# Park-A.net
KiCad netlist of a schematic drawn in EAGLE
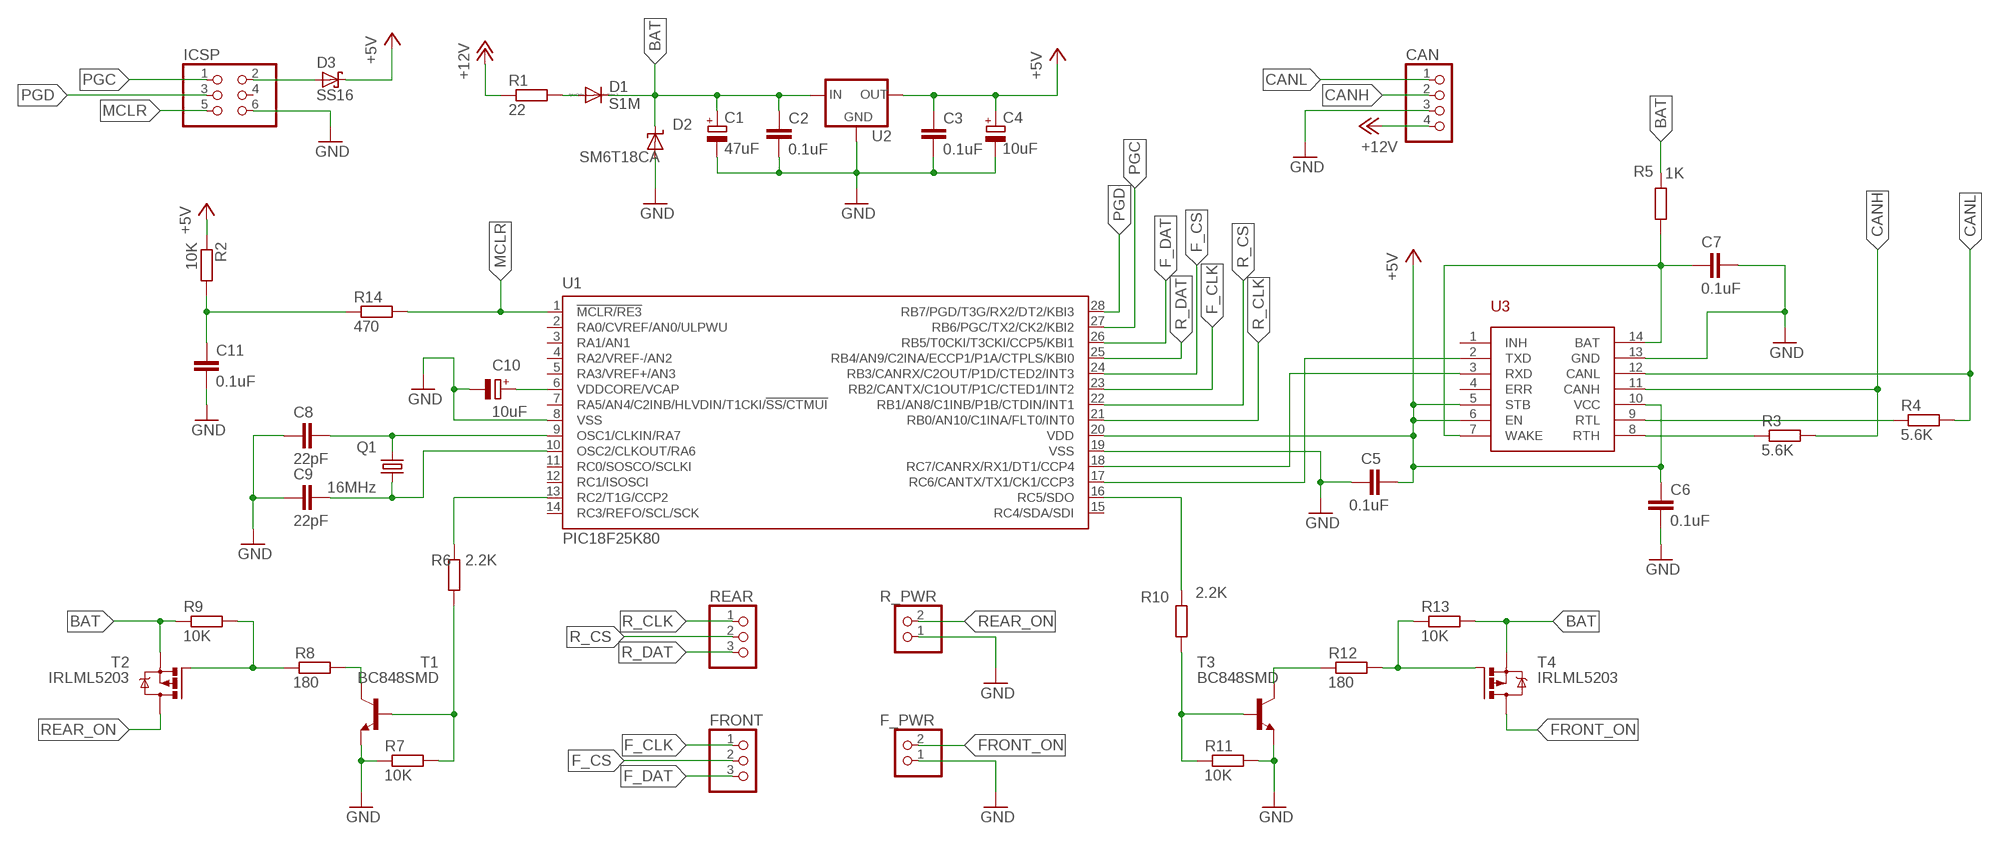
[diagram p0: schematic, sheet 1]

(export (version "E")
  (design (tool "Eeschema 10.0.6"))
  (components
    (comp (ref "C1")
      (value "47uF")
      (footprint "eagle-import:140CLH-0810")
      (libsource (lib "eagle-import") (part "CPOL-EU140CLH-0810"))
    )
    (comp (ref "C2")
      (value "0.1uF")
      (footprint "eagle-import:C0805")
      (libsource (lib "eagle-import") (part "C-EUC0805"))
    )
    (comp (ref "C3")
      (value "0.1uF")
      (footprint "eagle-import:C0805")
      (libsource (lib "eagle-import") (part "C-EUC0805"))
    )
    (comp (ref "C4")
      (value "10uF")
      (footprint "eagle-import:153CLV-0605")
      (libsource (lib "eagle-import") (part "CPOL-EU153CLV-0605"))
    )
    (comp (ref "C5")
      (value "0.1uF")
      (footprint "eagle-import:C0805")
      (libsource (lib "eagle-import") (part "C-EUC0805"))
    )
    (comp (ref "C6")
      (value "0.1uF")
      (footprint "eagle-import:C0805")
      (libsource (lib "eagle-import") (part "C-EUC0805"))
    )
    (comp (ref "C7")
      (value "0.1uF")
      (footprint "eagle-import:C0805")
      (libsource (lib "eagle-import") (part "C-EUC0805"))
    )
    (comp (ref "C8")
      (value "22pF")
      (footprint "eagle-import:C0805")
      (libsource (lib "eagle-import") (part "C-EUC0805"))
    )
    (comp (ref "C9")
      (value "22pF")
      (footprint "eagle-import:C0805")
      (libsource (lib "eagle-import") (part "C-EUC0805"))
    )
    (comp (ref "C10")
      (value "10uF")
      (footprint "eagle-import:SMC_A")
      (libsource (lib "eagle-import") (part "CPOL-EUSMCA"))
    )
    (comp (ref "C11")
      (value "0.1uF")
      (footprint "eagle-import:C0805")
      (libsource (lib "eagle-import") (part "C-EUC0805"))
    )
    (comp (ref "CAN")
      (value "PINHD-1X4")
      (footprint "eagle-import:1X04")
      (libsource (lib "eagle-import") (part "PINHD-1X4"))
    )
    (comp (ref "D1")
      (value "S1M")
      (footprint "eagle-import:SMA")
      (libsource (lib "eagle-import") (part "S1M"))
    )
    (comp (ref "D2")
      (value "SM6T18CA")
      (footprint "eagle-import:SMBJ")
      (libsource (lib "eagle-import") (part "SUPPRESSOR-SMBJ"))
    )
    (comp (ref "D3")
      (value "SS16")
      (footprint "eagle-import:DO214AC")
      (libsource (lib "eagle-import") (part "SS16"))
    )
    (comp (ref "FRONT")
      (value "PINHD-1X3")
      (footprint "eagle-import:1X03")
      (libsource (lib "eagle-import") (part "PINHD-1X3"))
    )
    (comp (ref "F_PWR")
      (value "PINHD-1X2")
      (footprint "eagle-import:1X02")
      (libsource (lib "eagle-import") (part "PINHD-1X2"))
    )
    (comp (ref "ICSP")
      (value "PINHD-2X3")
      (footprint "eagle-import:2X03")
      (libsource (lib "eagle-import") (part "PINHD-2X3"))
    )
    (comp (ref "Q1")
      (value "16MHz")
      (footprint "eagle-import:HC49_S")
      (libsource (lib "eagle-import") (part "CRYSTALHC49S"))
    )
    (comp (ref "R1")
      (value "22")
      (footprint "eagle-import:M1206")
      (libsource (lib "eagle-import") (part "R-EU_M1206"))
    )
    (comp (ref "R2")
      (value "10K")
      (footprint "eagle-import:R0805")
      (libsource (lib "eagle-import") (part "R-EU_R0805"))
    )
    (comp (ref "R3")
      (value "5.6K")
      (footprint "eagle-import:R0805")
      (libsource (lib "eagle-import") (part "R-EU_R0805"))
    )
    (comp (ref "R4")
      (value "5.6K")
      (footprint "eagle-import:R0805")
      (libsource (lib "eagle-import") (part "R-EU_R0805"))
    )
    (comp (ref "R5")
      (value "1K")
      (footprint "eagle-import:R0805")
      (libsource (lib "eagle-import") (part "R-EU_R0805"))
    )
    (comp (ref "R6")
      (value "2.2K")
      (footprint "eagle-import:R0805")
      (libsource (lib "eagle-import") (part "R-EU_R0805"))
    )
    (comp (ref "R7")
      (value "10K")
      (footprint "eagle-import:R0805")
      (libsource (lib "eagle-import") (part "R-EU_R0805"))
    )
    (comp (ref "R8")
      (value "180")
      (footprint "eagle-import:R0805")
      (libsource (lib "eagle-import") (part "R-EU_R0805"))
    )
    (comp (ref "R9")
      (value "10K")
      (footprint "eagle-import:R0805")
      (libsource (lib "eagle-import") (part "R-EU_R0805"))
    )
    (comp (ref "R10")
      (value "2.2K")
      (footprint "eagle-import:R0805")
      (libsource (lib "eagle-import") (part "R-EU_R0805"))
    )
    (comp (ref "R11")
      (value "10K")
      (footprint "eagle-import:R0805")
      (libsource (lib "eagle-import") (part "R-EU_R0805"))
    )
    (comp (ref "R12")
      (value "180")
      (footprint "eagle-import:R0805")
      (libsource (lib "eagle-import") (part "R-EU_R0805"))
    )
    (comp (ref "R13")
      (value "10K")
      (footprint "eagle-import:R0805")
      (libsource (lib "eagle-import") (part "R-EU_R0805"))
    )
    (comp (ref "R14")
      (value "470")
      (footprint "eagle-import:R0805")
      (libsource (lib "eagle-import") (part "R-EU_R0805"))
    )
    (comp (ref "REAR")
      (value "PINHD-1X3")
      (footprint "eagle-import:1X03")
      (libsource (lib "eagle-import") (part "PINHD-1X3"))
    )
    (comp (ref "R_PWR")
      (value "PINHD-1X2")
      (footprint "eagle-import:1X02")
      (libsource (lib "eagle-import") (part "PINHD-1X2"))
    )
    (comp (ref "T1")
      (value "BC848SMD")
      (footprint "eagle-import:SOT23")
      (libsource (lib "eagle-import") (part "BC848SMD"))
    )
    (comp (ref "T2")
      (value "IRLML5203")
      (footprint "eagle-import:SOT23")
      (libsource (lib "eagle-import") (part "IRLML5203"))
    )
    (comp (ref "T3")
      (value "BC848SMD")
      (footprint "eagle-import:SOT23")
      (libsource (lib "eagle-import") (part "BC848SMD"))
    )
    (comp (ref "T4")
      (value "IRLML5203")
      (footprint "eagle-import:SOT23")
      (libsource (lib "eagle-import") (part "IRLML5203"))
    )
    (comp (ref "U1")
      (value "PIC18F25K80")
      (footprint "eagle-import:SO28W")
      (libsource (lib "eagle-import") (part "PIC18F25K80"))
    )
    (comp (ref "U2")
      (value "78M05")
      (footprint "eagle-import:DPACK")
      (libsource (lib "eagle-import") (part "78M05"))
    )
    (comp (ref "U3")
      (value "TJA1055T")
      (footprint "eagle-import:SO-14W")
      (libsource (lib "eagle-import") (part "TJA1055T"))
    )
  )
  (nets
    (net (code "1") (name "+5V") (class "Default")
      (node (ref "C3") (pin "1") (pinfunction "1_1") (pintype "passive"))
      (node (ref "C4") (pin "+") (pinfunction "+_+") (pintype "passive"))
      (node (ref "C5") (pin "1") (pinfunction "1_1") (pintype "passive"))
      (node (ref "C6") (pin "1") (pinfunction "1_1") (pintype "passive"))
      (node (ref "D3") (pin "C") (pinfunction "C_C") (pintype "passive"))
      (node (ref "R2") (pin "1") (pinfunction "1_1") (pintype "passive"))
      (node (ref "U1") (pin "20") (pinfunction "VDD_20") (pintype "power_in"))
      (node (ref "U2") (pin "3") (pinfunction "OUT_3") (pintype "passive"))
      (node (ref "U3") (pin "10") (pinfunction "VCC_10") (pintype "power_in"))
      (node (ref "U3") (pin "5") (pinfunction "STB_5") (pintype "input"))
      (node (ref "U3") (pin "6") (pinfunction "EN_6") (pintype "input"))
    )
    (net (code "2") (name "+12V") (class "Default")
      (node (ref "CAN") (pin "4") (pinfunction "4_4") (pintype "passive"))
      (node (ref "R1") (pin "1") (pinfunction "1_1") (pintype "passive"))
    )
    (net (code "3") (name "BAT") (class "Default")
      (node (ref "C1") (pin "+") (pinfunction "+_+") (pintype "passive"))
      (node (ref "C2") (pin "1") (pinfunction "1_1") (pintype "passive"))
      (node (ref "D1") (pin "C") (pinfunction "C_C") (pintype "passive"))
      (node (ref "D2") (pin "C") (pinfunction "C_C") (pintype "passive"))
      (node (ref "R13") (pin "2") (pinfunction "2_2") (pintype "passive"))
      (node (ref "R5") (pin "2") (pinfunction "2_2") (pintype "passive"))
      (node (ref "R9") (pin "1") (pinfunction "1_1") (pintype "passive"))
      (node (ref "T2") (pin "2") (pinfunction "S_2") (pintype "passive"))
      (node (ref "T4") (pin "2") (pinfunction "S_2") (pintype "passive"))
      (node (ref "U2") (pin "1") (pinfunction "IN_1") (pintype "input"))
    )
    (net (code "4") (name "CANH") (class "Default")
      (node (ref "CAN") (pin "2") (pinfunction "2_2") (pintype "passive"))
      (node (ref "R3") (pin "2") (pinfunction "2_2") (pintype "passive"))
      (node (ref "U3") (pin "11") (pinfunction "CANH_11") (pintype "bidirectional"))
    )
    (net (code "5") (name "CANL") (class "Default")
      (node (ref "CAN") (pin "1") (pinfunction "1_1") (pintype "passive"))
      (node (ref "R4") (pin "2") (pinfunction "2_2") (pintype "passive"))
      (node (ref "U3") (pin "12") (pinfunction "CANL_12") (pintype "bidirectional"))
    )
    (net (code "6") (name "FRONT_ON") (class "Default")
      (node (ref "F_PWR") (pin "2") (pinfunction "2_2") (pintype "passive"))
      (node (ref "T4") (pin "3") (pinfunction "D_3") (pintype "passive"))
    )
    (net (code "7") (name "F_CLK") (class "Default")
      (node (ref "FRONT") (pin "1") (pinfunction "1_1") (pintype "passive"))
      (node (ref "U1") (pin "23") (pinfunction "RB2/CANTX/C1OUT/P1C/CTED1/INT2_23") (pintype "bidirectional"))
    )
    (net (code "8") (name "F_CS") (class "Default")
      (node (ref "FRONT") (pin "2") (pinfunction "2_2") (pintype "passive"))
      (node (ref "U1") (pin "24") (pinfunction "RB3/CANRX/C2OUT/P1D/CTED2/INT3_24") (pintype "bidirectional"))
    )
    (net (code "9") (name "F_DAT") (class "Default")
      (node (ref "FRONT") (pin "3") (pinfunction "3_3") (pintype "passive"))
      (node (ref "U1") (pin "26") (pinfunction "RB5/T0CKI/T3CKI/CCP5/KBI1_26") (pintype "bidirectional"))
    )
    (net (code "10") (name "GND") (class "Default")
      (node (ref "C1") (pin "-") (pinfunction "-_-") (pintype "passive"))
      (node (ref "C10") (pin "-") (pinfunction "-_-") (pintype "passive"))
      (node (ref "C11") (pin "2") (pinfunction "2_2") (pintype "passive"))
      (node (ref "C2") (pin "2") (pinfunction "2_2") (pintype "passive"))
      (node (ref "C3") (pin "2") (pinfunction "2_2") (pintype "passive"))
      (node (ref "C4") (pin "-") (pinfunction "-_-") (pintype "passive"))
      (node (ref "C5") (pin "2") (pinfunction "2_2") (pintype "passive"))
      (node (ref "C6") (pin "2") (pinfunction "2_2") (pintype "passive"))
      (node (ref "C7") (pin "2") (pinfunction "2_2") (pintype "passive"))
      (node (ref "C8") (pin "1") (pinfunction "1_1") (pintype "passive"))
      (node (ref "C9") (pin "1") (pinfunction "1_1") (pintype "passive"))
      (node (ref "CAN") (pin "3") (pinfunction "3_3") (pintype "passive"))
      (node (ref "D2") (pin "A") (pinfunction "A_A") (pintype "passive"))
      (node (ref "F_PWR") (pin "1") (pinfunction "1_1") (pintype "passive"))
      (node (ref "ICSP") (pin "6") (pinfunction "6_6") (pintype "passive"))
      (node (ref "R11") (pin "2") (pinfunction "2_2") (pintype "passive"))
      (node (ref "R7") (pin "1") (pinfunction "1_1") (pintype "passive"))
      (node (ref "R_PWR") (pin "1") (pinfunction "1_1") (pintype "passive"))
      (node (ref "T1") (pin "2") (pinfunction "E_2") (pintype "passive"))
      (node (ref "T3") (pin "2") (pinfunction "E_2") (pintype "passive"))
      (node (ref "U1") (pin "19") (pinfunction "VSS_19") (pintype "power_in"))
      (node (ref "U1") (pin "8") (pinfunction "VSS_8") (pintype "power_in"))
      (node (ref "U2") (pin "4") (pinfunction "GND_4") (pintype "input"))
      (node (ref "U3") (pin "13") (pinfunction "GND_13") (pintype "power_in"))
    )
    (net (code "11") (name "MCLR") (class "Default")
      (node (ref "ICSP") (pin "5") (pinfunction "5_5") (pintype "passive"))
      (node (ref "R14") (pin "2") (pinfunction "2_2") (pintype "passive"))
      (node (ref "U1") (pin "1") (pinfunction "~{MCLR/RE3}_1") (pintype "input"))
    )
    (net (code "12") (name "Net-(C11-Pad1)") (class "Default")
      (node (ref "C11") (pin "1") (pinfunction "1_1") (pintype "passive"))
      (node (ref "R14") (pin "1") (pinfunction "1_1") (pintype "passive"))
      (node (ref "R2") (pin "2") (pinfunction "2_2") (pintype "passive"))
    )
    (net (code "13") (name "Net-(D1-PadA)") (class "Default")
      (node (ref "D1") (pin "A") (pinfunction "A_A") (pintype "passive"))
      (node (ref "R1") (pin "2") (pinfunction "2_2") (pintype "passive"))
    )
    (net (code "14") (name "Net-(D3-PadA)") (class "Default")
      (node (ref "D3") (pin "A") (pinfunction "A_A") (pintype "passive"))
      (node (ref "ICSP") (pin "2") (pinfunction "2_2") (pintype "passive"))
    )
    (net (code "15") (name "Net-(T1-B)") (class "Default")
      (node (ref "R6") (pin "1") (pinfunction "1_1") (pintype "passive"))
      (node (ref "R7") (pin "2") (pinfunction "2_2") (pintype "passive"))
      (node (ref "T1") (pin "1") (pinfunction "B_1") (pintype "passive"))
    )
    (net (code "16") (name "Net-(T1-C)") (class "Default")
      (node (ref "R8") (pin "1") (pinfunction "1_1") (pintype "passive"))
      (node (ref "T1") (pin "3") (pinfunction "C_3") (pintype "passive"))
    )
    (net (code "17") (name "Net-(T2-G)") (class "Default")
      (node (ref "R8") (pin "2") (pinfunction "2_2") (pintype "passive"))
      (node (ref "R9") (pin "2") (pinfunction "2_2") (pintype "passive"))
      (node (ref "T2") (pin "1") (pinfunction "G_1") (pintype "passive"))
    )
    (net (code "18") (name "Net-(T3-B)") (class "Default")
      (node (ref "R10") (pin "1") (pinfunction "1_1") (pintype "passive"))
      (node (ref "R11") (pin "1") (pinfunction "1_1") (pintype "passive"))
      (node (ref "T3") (pin "1") (pinfunction "B_1") (pintype "passive"))
    )
    (net (code "19") (name "Net-(T3-C)") (class "Default")
      (node (ref "R12") (pin "1") (pinfunction "1_1") (pintype "passive"))
      (node (ref "T3") (pin "3") (pinfunction "C_3") (pintype "passive"))
    )
    (net (code "20") (name "Net-(T4-G)") (class "Default")
      (node (ref "R12") (pin "2") (pinfunction "2_2") (pintype "passive"))
      (node (ref "R13") (pin "1") (pinfunction "1_1") (pintype "passive"))
      (node (ref "T4") (pin "1") (pinfunction "G_1") (pintype "passive"))
    )
    (net (code "21") (name "Net-(U1-OSC1{slash}CLKIN{slash}RA7)") (class "Default")
      (node (ref "C8") (pin "2") (pinfunction "2_2") (pintype "passive"))
      (node (ref "Q1") (pin "1") (pinfunction "1_1") (pintype "passive"))
      (node (ref "U1") (pin "9") (pinfunction "OSC1/CLKIN/RA7_9") (pintype "input"))
    )
    (net (code "22") (name "Net-(U1-OSC2{slash}CLKOUT{slash}RA6)") (class "Default")
      (node (ref "C9") (pin "2") (pinfunction "2_2") (pintype "passive"))
      (node (ref "Q1") (pin "2") (pinfunction "2_2") (pintype "passive"))
      (node (ref "U1") (pin "10") (pinfunction "OSC2/CLKOUT/RA6_10") (pintype "output"))
    )
    (net (code "23") (name "Net-(U1-RC2{slash}T1G{slash}CCP2)") (class "Default")
      (node (ref "R6") (pin "2") (pinfunction "2_2") (pintype "passive"))
      (node (ref "U1") (pin "13") (pinfunction "RC2/T1G/CCP2_13") (pintype "bidirectional"))
    )
    (net (code "24") (name "Net-(U1-RC5{slash}SDO)") (class "Default")
      (node (ref "R10") (pin "2") (pinfunction "2_2") (pintype "passive"))
      (node (ref "U1") (pin "16") (pinfunction "RC5/SDO_16") (pintype "bidirectional"))
    )
    (net (code "25") (name "Net-(U1-RC6{slash}CANTX{slash}TX1{slash}CK1{slash}CCP3)") (class "Default")
      (node (ref "U1") (pin "17") (pinfunction "RC6/CANTX/TX1/CK1/CCP3_17") (pintype "bidirectional"))
      (node (ref "U3") (pin "2") (pinfunction "TXD_2") (pintype "bidirectional"))
    )
    (net (code "26") (name "Net-(U1-RC7{slash}CANRX{slash}RX1{slash}DT1{slash}CCP4)") (class "Default")
      (node (ref "U1") (pin "18") (pinfunction "RC7/CANRX/RX1/DT1/CCP4_18") (pintype "bidirectional"))
      (node (ref "U3") (pin "3") (pinfunction "RXD_3") (pintype "bidirectional"))
    )
    (net (code "27") (name "Net-(U1-VDDCORE{slash}VCAP)") (class "Default")
      (node (ref "C10") (pin "+") (pinfunction "+_+") (pintype "passive"))
      (node (ref "U1") (pin "6") (pinfunction "VDDCORE/VCAP_6") (pintype "bidirectional"))
    )
    (net (code "28") (name "Net-(U3-BAT)") (class "Default")
      (node (ref "C7") (pin "1") (pinfunction "1_1") (pintype "passive"))
      (node (ref "R5") (pin "1") (pinfunction "1_1") (pintype "passive"))
      (node (ref "U3") (pin "14") (pinfunction "BAT_14") (pintype "input"))
      (node (ref "U3") (pin "7") (pinfunction "WAKE_7") (pintype "input"))
    )
    (net (code "29") (name "Net-(U3-RTH)") (class "Default")
      (node (ref "R3") (pin "1") (pinfunction "1_1") (pintype "passive"))
      (node (ref "U3") (pin "8") (pinfunction "RTH_8") (pintype "bidirectional"))
    )
    (net (code "30") (name "Net-(U3-RTL)") (class "Default")
      (node (ref "R4") (pin "1") (pinfunction "1_1") (pintype "passive"))
      (node (ref "U3") (pin "9") (pinfunction "RTL_9") (pintype "bidirectional"))
    )
    (net (code "31") (name "PGC") (class "Default")
      (node (ref "ICSP") (pin "1") (pinfunction "1_1") (pintype "passive"))
      (node (ref "U1") (pin "27") (pinfunction "RB6/PGC/TX2/CK2/KBI2_27") (pintype "bidirectional"))
    )
    (net (code "32") (name "PGD") (class "Default")
      (node (ref "ICSP") (pin "3") (pinfunction "3_3") (pintype "passive"))
      (node (ref "U1") (pin "28") (pinfunction "RB7/PGD/T3G/RX2/DT2/KBI3_28") (pintype "bidirectional"))
    )
    (net (code "33") (name "REAR_ON") (class "Default")
      (node (ref "R_PWR") (pin "2") (pinfunction "2_2") (pintype "passive"))
      (node (ref "T2") (pin "3") (pinfunction "D_3") (pintype "passive"))
    )
    (net (code "34") (name "R_CLK") (class "Default")
      (node (ref "REAR") (pin "1") (pinfunction "1_1") (pintype "passive"))
      (node (ref "U1") (pin "21") (pinfunction "RB0/AN10/C1INA/FLT0/INT0_21") (pintype "bidirectional"))
    )
    (net (code "35") (name "R_CS") (class "Default")
      (node (ref "REAR") (pin "2") (pinfunction "2_2") (pintype "passive"))
      (node (ref "U1") (pin "22") (pinfunction "RB1/AN8/C1INB/P1B/CTDIN/INT1_22") (pintype "bidirectional"))
    )
    (net (code "36") (name "R_DAT") (class "Default")
      (node (ref "REAR") (pin "3") (pinfunction "3_3") (pintype "passive"))
      (node (ref "U1") (pin "25") (pinfunction "RB4/AN9/C2INA/ECCP1/P1A/CTPLS/KBI0_25") (pintype "bidirectional"))
    )
    (net (code "37") (name "unconnected-(ICSP-Pad4)") (class "Default")
      (node (ref "ICSP") (pin "4") (pinfunction "4_4") (pintype "passive"))
    )
    (net (code "38") (name "unconnected-(U1-RA0{slash}CVREF{slash}AN0{slash}ULPWU-Pad2)") (class "Default")
      (node (ref "U1") (pin "2") (pinfunction "RA0/CVREF/AN0/ULPWU_2") (pintype "bidirectional"))
    )
    (net (code "39") (name "unconnected-(U1-RA1{slash}AN1-Pad3)") (class "Default")
      (node (ref "U1") (pin "3") (pinfunction "RA1/AN1_3") (pintype "bidirectional"))
    )
    (net (code "40") (name "unconnected-(U1-RA2{slash}VREF-{slash}AN2-Pad4)") (class "Default")
      (node (ref "U1") (pin "4") (pinfunction "RA2/VREF-/AN2_4") (pintype "bidirectional"))
    )
    (net (code "41") (name "unconnected-(U1-RA3{slash}VREF+{slash}AN3-Pad5)") (class "Default")
      (node (ref "U1") (pin "5") (pinfunction "RA3/VREF+/AN3_5") (pintype "bidirectional"))
    )
    (net (code "42") (name "unconnected-(U1-RA5{slash}AN4{slash}C2INB{slash}HLVDIN{slash}T1CKI{slash}~{SS{slash}CTMUI}-Pad7)") (class "Default")
      (node (ref "U1") (pin "7") (pinfunction "RA5/AN4/C2INB/HLVDIN/T1CKI/~{SS/CTMUI}_7") (pintype "bidirectional"))
    )
    (net (code "43") (name "unconnected-(U1-RC0{slash}SOSCO{slash}SCLKI-Pad11)") (class "Default")
      (node (ref "U1") (pin "11") (pinfunction "RC0/SOSCO/SCLKI_11") (pintype "bidirectional"))
    )
    (net (code "44") (name "unconnected-(U1-RC1{slash}ISOSCI-Pad12)") (class "Default")
      (node (ref "U1") (pin "12") (pinfunction "RC1/ISOSCI_12") (pintype "bidirectional"))
    )
    (net (code "45") (name "unconnected-(U1-RC3{slash}REFO{slash}SCL{slash}SCK-Pad14)") (class "Default")
      (node (ref "U1") (pin "14") (pinfunction "RC3/REFO/SCL/SCK_14") (pintype "bidirectional"))
    )
    (net (code "46") (name "unconnected-(U1-RC4{slash}SDA{slash}SDI-Pad15)") (class "Default")
      (node (ref "U1") (pin "15") (pinfunction "RC4/SDA/SDI_15") (pintype "bidirectional"))
    )
    (net (code "47") (name "unconnected-(U3-ERR-Pad4)") (class "Default")
      (node (ref "U3") (pin "4") (pinfunction "ERR_4") (pintype "output"))
    )
    (net (code "48") (name "unconnected-(U3-INH-Pad1)") (class "Default")
      (node (ref "U3") (pin "1") (pinfunction "INH_1") (pintype "output"))
    )
  )
)
